# MSXIoT.net
KiCad netlist of a schematic drawn in EAGLE
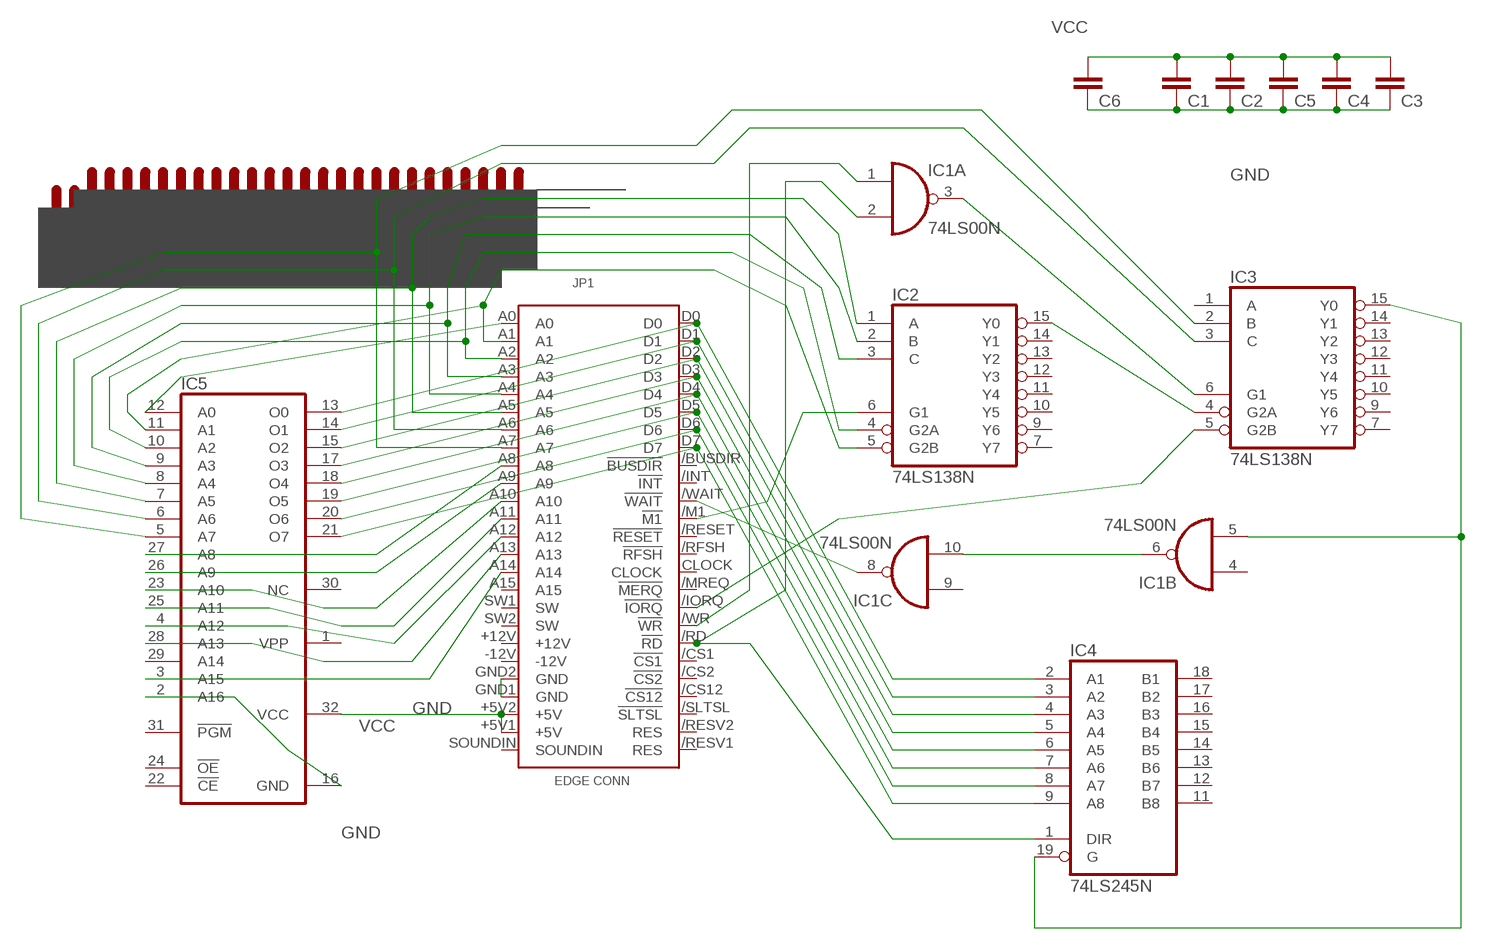
[diagram p0: schematic, sheet 1]

(export (version "E")
  (design (tool "Eeschema 10.0.6"))
  (components
    (comp (ref "C1")
      (value "C2.5/2")
      (footprint "eagle-import:C2.5-2")
      (libsource (lib "eagle-import") (part "C2.5/2"))
    )
    (comp (ref "C2")
      (value "C2,5-3")
      (footprint "eagle-import:C2.5-3")
      (libsource (lib "eagle-import") (part "C2,5-3"))
    )
    (comp (ref "C3")
      (value "C2,5-3")
      (footprint "eagle-import:C2.5-3")
      (libsource (lib "eagle-import") (part "C2,5-3"))
    )
    (comp (ref "C4")
      (value "C2,5-3")
      (footprint "eagle-import:C2.5-3")
      (libsource (lib "eagle-import") (part "C2,5-3"))
    )
    (comp (ref "C5")
      (value "C2,5-3")
      (footprint "eagle-import:C2.5-3")
      (libsource (lib "eagle-import") (part "C2,5-3"))
    )
    (comp (ref "C6")
      (value "C2.5/6")
      (footprint "eagle-import:C2.5-6")
      (libsource (lib "eagle-import") (part "C2.5/6"))
    )
    (comp (ref "IC1")
      (value "74LS00N")
      (footprint "eagle-import:DIL14")
      (libsource (lib "eagle-import") (part "7400NLS"))
    )
    (comp (ref "IC2")
      (value "74LS138N")
      (footprint "eagle-import:DIL16")
      (libsource (lib "eagle-import") (part "74138NLS"))
    )
    (comp (ref "IC3")
      (value "74LS138N")
      (footprint "eagle-import:DIL16")
      (libsource (lib "eagle-import") (part "74138NLS"))
    )
    (comp (ref "IC4")
      (value "74LS245N")
      (footprint "eagle-import:DIL20")
      (libsource (lib "eagle-import") (part "74245NLS"))
    )
    (comp (ref "IC5")
      (value "27C1001A")
      (footprint "eagle-import:DIL32")
      (fields (field (name "MPN") "M27C1001-15F1"))
      (libsource (lib "eagle-import") (part "27C1001A"))
    )
    (comp (ref "JP1")
      (value "MSXCART")
      (footprint "eagle-import:MSXCART")
      (libsource (lib "eagle-import") (part "MSXCART"))
    )
  )
  (nets
    (net (code "1") (name "/+12V") (class "Default")
      (node (ref "JP1") (pin "+12V") (pinfunction "+12V_+12V") (pintype "power_in"))
    )
    (net (code "2") (name "/-12V") (class "Default")
      (node (ref "JP1") (pin "-12V") (pinfunction "-12V_-12V") (pintype "power_in"))
    )
    (net (code "3") (name "/GND") (class "Default")
      (node (ref "C1") (pin "2") (pinfunction "2_2") (pintype "passive"))
      (node (ref "C2") (pin "2") (pinfunction "2_2") (pintype "passive"))
      (node (ref "C3") (pin "2") (pinfunction "2_2") (pintype "passive"))
      (node (ref "C4") (pin "2") (pinfunction "2_2") (pintype "passive"))
      (node (ref "C5") (pin "2") (pinfunction "2_2") (pintype "passive"))
      (node (ref "C6") (pin "2") (pinfunction "2_2") (pintype "passive"))
      (node (ref "IC5") (pin "16") (pinfunction "GND_16") (pintype "power_in"))
      (node (ref "IC5") (pin "2") (pinfunction "A16_2") (pintype "input"))
      (node (ref "JP1") (pin "GND1") (pinfunction "GND_GND1") (pintype "power_in"))
      (node (ref "JP1") (pin "GND2") (pinfunction "GND_GND2") (pintype "power_in"))
    )
    (net (code "4") (name "/VCC") (class "Default")
      (node (ref "C1") (pin "1") (pinfunction "1_1") (pintype "passive"))
      (node (ref "C2") (pin "1") (pinfunction "1_1") (pintype "passive"))
      (node (ref "C3") (pin "1") (pinfunction "1_1") (pintype "passive"))
      (node (ref "C4") (pin "1") (pinfunction "1_1") (pintype "passive"))
      (node (ref "C5") (pin "1") (pinfunction "1_1") (pintype "passive"))
      (node (ref "C6") (pin "1") (pinfunction "1_1") (pintype "passive"))
      (node (ref "IC5") (pin "32") (pinfunction "VCC_32") (pintype "power_in"))
      (node (ref "JP1") (pin "+5V1") (pinfunction "+5V_+5V1") (pintype "power_in"))
      (node (ref "JP1") (pin "+5V2") (pinfunction "+5V_+5V2") (pintype "power_in"))
    )
    (net (code "5") (name "Net-(IC1A-I0)") (class "Default")
      (node (ref "IC1") (pin "1") (pinfunction "I0_1") (pintype "input"))
      (node (ref "JP1") (pin "/WR") (pinfunction "~{WR}_/WR") (pintype "output"))
    )
    (net (code "6") (name "Net-(IC1A-I1)") (class "Default")
      (node (ref "IC1") (pin "2") (pinfunction "I1_2") (pintype "input"))
      (node (ref "IC4") (pin "1") (pinfunction "DIR_1") (pintype "input"))
      (node (ref "JP1") (pin "/RD") (pinfunction "~{RD}_/RD") (pintype "output"))
    )
    (net (code "7") (name "Net-(IC1A-O)") (class "Default")
      (node (ref "IC1") (pin "3") (pinfunction "O_3") (pintype "output"))
      (node (ref "IC3") (pin "6") (pinfunction "G1_6") (pintype "input"))
    )
    (net (code "8") (name "Net-(IC1B-I1)") (class "Default")
      (node (ref "IC1") (pin "5") (pinfunction "I1_5") (pintype "input"))
      (node (ref "IC3") (pin "15") (pinfunction "Y0_15") (pintype "output"))
      (node (ref "IC4") (pin "19") (pinfunction "G_19") (pintype "input"))
    )
    (net (code "9") (name "Net-(IC1B-O)") (class "Default")
      (node (ref "IC1") (pin "10") (pinfunction "I1_10") (pintype "input"))
      (node (ref "IC1") (pin "6") (pinfunction "O_6") (pintype "output"))
    )
    (net (code "10") (name "Net-(IC1C-O)") (class "Default")
      (node (ref "IC1") (pin "8") (pinfunction "O_8") (pintype "output"))
      (node (ref "JP1") (pin "/WAIT") (pinfunction "~{WAIT}_/WAIT") (pintype "open_collector"))
    )
    (net (code "11") (name "Net-(IC2A-A)") (class "Default")
      (node (ref "IC2") (pin "1") (pinfunction "A_1") (pintype "input"))
      (node (ref "IC5") (pin "7") (pinfunction "A5_7") (pintype "input"))
      (node (ref "JP1") (pin "A5") (pinfunction "A5_A5") (pintype "output"))
    )
    (net (code "12") (name "Net-(IC2A-B)") (class "Default")
      (node (ref "IC2") (pin "2") (pinfunction "B_2") (pintype "input"))
      (node (ref "IC5") (pin "8") (pinfunction "A4_8") (pintype "input"))
      (node (ref "JP1") (pin "A4") (pinfunction "A4_A4") (pintype "output"))
    )
    (net (code "13") (name "Net-(IC2A-C)") (class "Default")
      (node (ref "IC2") (pin "3") (pinfunction "C_3") (pintype "input"))
      (node (ref "IC5") (pin "9") (pinfunction "A3_9") (pintype "input"))
      (node (ref "JP1") (pin "A3") (pinfunction "A3_A3") (pintype "output"))
    )
    (net (code "14") (name "Net-(IC2A-G1)") (class "Default")
      (node (ref "IC2") (pin "6") (pinfunction "G1_6") (pintype "input"))
      (node (ref "JP1") (pin "/M1") (pinfunction "~{M1}_/M1") (pintype "output"))
    )
    (net (code "15") (name "Net-(IC2A-G2A)") (class "Default")
      (node (ref "IC2") (pin "4") (pinfunction "G2A_4") (pintype "input"))
      (node (ref "IC5") (pin "10") (pinfunction "A2_10") (pintype "input"))
      (node (ref "JP1") (pin "A2") (pinfunction "A2_A2") (pintype "output"))
    )
    (net (code "16") (name "Net-(IC2A-G2B)") (class "Default")
      (node (ref "IC2") (pin "5") (pinfunction "G2B_5") (pintype "input"))
      (node (ref "IC5") (pin "11") (pinfunction "A1_11") (pintype "input"))
      (node (ref "JP1") (pin "A1") (pinfunction "A1_A1") (pintype "output"))
    )
    (net (code "17") (name "Net-(IC2A-Y0)") (class "Default")
      (node (ref "IC2") (pin "15") (pinfunction "Y0_15") (pintype "output"))
      (node (ref "IC3") (pin "4") (pinfunction "G2A_4") (pintype "input"))
    )
    (net (code "18") (name "Net-(IC3A-B)") (class "Default")
      (node (ref "IC3") (pin "2") (pinfunction "B_2") (pintype "input"))
      (node (ref "IC5") (pin "5") (pinfunction "A7_5") (pintype "input"))
      (node (ref "JP1") (pin "A7") (pinfunction "A7_A7") (pintype "output"))
    )
    (net (code "19") (name "Net-(IC3A-C)") (class "Default")
      (node (ref "IC3") (pin "3") (pinfunction "C_3") (pintype "input"))
      (node (ref "IC5") (pin "6") (pinfunction "A6_6") (pintype "input"))
      (node (ref "JP1") (pin "A6") (pinfunction "A6_A6") (pintype "output"))
    )
    (net (code "20") (name "Net-(IC3A-G2B)") (class "Default")
      (node (ref "IC3") (pin "5") (pinfunction "G2B_5") (pintype "input"))
      (node (ref "JP1") (pin "/IORQ") (pinfunction "~{IORQ}_/IORQ") (pintype "output"))
    )
    (net (code "21") (name "Net-(IC4A-A1)") (class "Default")
      (node (ref "IC4") (pin "2") (pinfunction "A1_2") (pintype "bidirectional"))
      (node (ref "IC5") (pin "13") (pinfunction "O0_13") (pintype "tri_state"))
      (node (ref "JP1") (pin "D0") (pinfunction "D0_D0") (pintype "bidirectional"))
    )
    (net (code "22") (name "Net-(IC4A-A2)") (class "Default")
      (node (ref "IC4") (pin "3") (pinfunction "A2_3") (pintype "bidirectional"))
      (node (ref "IC5") (pin "14") (pinfunction "O1_14") (pintype "tri_state"))
      (node (ref "JP1") (pin "D1") (pinfunction "D1_D1") (pintype "bidirectional"))
    )
    (net (code "23") (name "Net-(IC4A-A3)") (class "Default")
      (node (ref "IC4") (pin "4") (pinfunction "A3_4") (pintype "bidirectional"))
      (node (ref "IC5") (pin "15") (pinfunction "O2_15") (pintype "tri_state"))
      (node (ref "JP1") (pin "D2") (pinfunction "D2_D2") (pintype "bidirectional"))
    )
    (net (code "24") (name "Net-(IC4A-A4)") (class "Default")
      (node (ref "IC4") (pin "5") (pinfunction "A4_5") (pintype "bidirectional"))
      (node (ref "IC5") (pin "17") (pinfunction "O3_17") (pintype "tri_state"))
      (node (ref "JP1") (pin "D3") (pinfunction "D3_D3") (pintype "bidirectional"))
    )
    (net (code "25") (name "Net-(IC4A-A5)") (class "Default")
      (node (ref "IC4") (pin "6") (pinfunction "A5_6") (pintype "bidirectional"))
      (node (ref "IC5") (pin "18") (pinfunction "O4_18") (pintype "tri_state"))
      (node (ref "JP1") (pin "D4") (pinfunction "D4_D4") (pintype "bidirectional"))
    )
    (net (code "26") (name "Net-(IC4A-A6)") (class "Default")
      (node (ref "IC4") (pin "7") (pinfunction "A6_7") (pintype "bidirectional"))
      (node (ref "IC5") (pin "19") (pinfunction "O5_19") (pintype "tri_state"))
      (node (ref "JP1") (pin "D5") (pinfunction "D5_D5") (pintype "bidirectional"))
    )
    (net (code "27") (name "Net-(IC4A-A7)") (class "Default")
      (node (ref "IC4") (pin "8") (pinfunction "A7_8") (pintype "bidirectional"))
      (node (ref "IC5") (pin "20") (pinfunction "O6_20") (pintype "tri_state"))
      (node (ref "JP1") (pin "D6") (pinfunction "D6_D6") (pintype "bidirectional"))
    )
    (net (code "28") (name "Net-(IC4A-A8)") (class "Default")
      (node (ref "IC4") (pin "9") (pinfunction "A8_9") (pintype "bidirectional"))
      (node (ref "IC5") (pin "21") (pinfunction "O7_21") (pintype "tri_state"))
      (node (ref "JP1") (pin "D7") (pinfunction "D7_D7") (pintype "bidirectional"))
    )
    (net (code "29") (name "Net-(IC5-A0)") (class "Default")
      (node (ref "IC5") (pin "12") (pinfunction "A0_12") (pintype "input"))
      (node (ref "JP1") (pin "A0") (pinfunction "A0_A0") (pintype "output"))
    )
    (net (code "30") (name "Net-(IC5-A8)") (class "Default")
      (node (ref "IC5") (pin "27") (pinfunction "A8_27") (pintype "input"))
      (node (ref "JP1") (pin "A8") (pinfunction "A8_A8") (pintype "output"))
    )
    (net (code "31") (name "Net-(IC5-A9)") (class "Default")
      (node (ref "IC5") (pin "26") (pinfunction "A9_26") (pintype "input"))
      (node (ref "JP1") (pin "A9") (pinfunction "A9_A9") (pintype "output"))
    )
    (net (code "32") (name "Net-(IC5-A10)") (class "Default")
      (node (ref "IC5") (pin "23") (pinfunction "A10_23") (pintype "input"))
      (node (ref "JP1") (pin "A10") (pinfunction "A10_A10") (pintype "output"))
    )
    (net (code "33") (name "Net-(IC5-A11)") (class "Default")
      (node (ref "IC5") (pin "25") (pinfunction "A11_25") (pintype "input"))
      (node (ref "JP1") (pin "A11") (pinfunction "A11_A11") (pintype "output"))
    )
    (net (code "34") (name "Net-(IC5-A12)") (class "Default")
      (node (ref "IC5") (pin "4") (pinfunction "A12_4") (pintype "input"))
      (node (ref "JP1") (pin "A12") (pinfunction "A12_A12") (pintype "output"))
    )
    (net (code "35") (name "Net-(IC5-A13)") (class "Default")
      (node (ref "IC5") (pin "28") (pinfunction "A13_28") (pintype "input"))
      (node (ref "JP1") (pin "A13") (pinfunction "A13_A13") (pintype "output"))
    )
    (net (code "36") (name "Net-(IC5-A15)") (class "Default")
      (node (ref "IC5") (pin "3") (pinfunction "A15_3") (pintype "input"))
      (node (ref "JP1") (pin "A14") (pinfunction "A14_A14") (pintype "output"))
    )
    (net (code "37") (name "unconnected-(IC1B-I0-Pad4)") (class "Default")
      (node (ref "IC1") (pin "4") (pinfunction "I0_4") (pintype "input"))
    )
    (net (code "38") (name "unconnected-(IC1C-I0-Pad9)") (class "Default")
      (node (ref "IC1") (pin "9") (pinfunction "I0_9") (pintype "input"))
    )
    (net (code "39") (name "unconnected-(IC2A-Y1-Pad14)") (class "Default")
      (node (ref "IC2") (pin "14") (pinfunction "Y1_14") (pintype "output"))
    )
    (net (code "40") (name "unconnected-(IC2A-Y2-Pad13)") (class "Default")
      (node (ref "IC2") (pin "13") (pinfunction "Y2_13") (pintype "output"))
    )
    (net (code "41") (name "unconnected-(IC2A-Y3-Pad12)") (class "Default")
      (node (ref "IC2") (pin "12") (pinfunction "Y3_12") (pintype "output"))
    )
    (net (code "42") (name "unconnected-(IC2A-Y4-Pad11)") (class "Default")
      (node (ref "IC2") (pin "11") (pinfunction "Y4_11") (pintype "output"))
    )
    (net (code "43") (name "unconnected-(IC2A-Y5-Pad10)") (class "Default")
      (node (ref "IC2") (pin "10") (pinfunction "Y5_10") (pintype "output"))
    )
    (net (code "44") (name "unconnected-(IC2A-Y6-Pad9)") (class "Default")
      (node (ref "IC2") (pin "9") (pinfunction "Y6_9") (pintype "output"))
    )
    (net (code "45") (name "unconnected-(IC2A-Y7-Pad7)") (class "Default")
      (node (ref "IC2") (pin "7") (pinfunction "Y7_7") (pintype "output"))
    )
    (net (code "46") (name "unconnected-(IC3A-A-Pad1)") (class "Default")
      (node (ref "IC3") (pin "1") (pinfunction "A_1") (pintype "input"))
    )
    (net (code "47") (name "unconnected-(IC3A-Y1-Pad14)") (class "Default")
      (node (ref "IC3") (pin "14") (pinfunction "Y1_14") (pintype "output"))
    )
    (net (code "48") (name "unconnected-(IC3A-Y2-Pad13)") (class "Default")
      (node (ref "IC3") (pin "13") (pinfunction "Y2_13") (pintype "output"))
    )
    (net (code "49") (name "unconnected-(IC3A-Y3-Pad12)") (class "Default")
      (node (ref "IC3") (pin "12") (pinfunction "Y3_12") (pintype "output"))
    )
    (net (code "50") (name "unconnected-(IC3A-Y4-Pad11)") (class "Default")
      (node (ref "IC3") (pin "11") (pinfunction "Y4_11") (pintype "output"))
    )
    (net (code "51") (name "unconnected-(IC3A-Y5-Pad10)") (class "Default")
      (node (ref "IC3") (pin "10") (pinfunction "Y5_10") (pintype "output"))
    )
    (net (code "52") (name "unconnected-(IC3A-Y6-Pad9)") (class "Default")
      (node (ref "IC3") (pin "9") (pinfunction "Y6_9") (pintype "output"))
    )
    (net (code "53") (name "unconnected-(IC3A-Y7-Pad7)") (class "Default")
      (node (ref "IC3") (pin "7") (pinfunction "Y7_7") (pintype "output"))
    )
    (net (code "54") (name "unconnected-(IC4A-B1-Pad18)") (class "Default")
      (node (ref "IC4") (pin "18") (pinfunction "B1_18") (pintype "bidirectional"))
    )
    (net (code "55") (name "unconnected-(IC4A-B2-Pad17)") (class "Default")
      (node (ref "IC4") (pin "17") (pinfunction "B2_17") (pintype "bidirectional"))
    )
    (net (code "56") (name "unconnected-(IC4A-B3-Pad16)") (class "Default")
      (node (ref "IC4") (pin "16") (pinfunction "B3_16") (pintype "bidirectional"))
    )
    (net (code "57") (name "unconnected-(IC4A-B4-Pad15)") (class "Default")
      (node (ref "IC4") (pin "15") (pinfunction "B4_15") (pintype "bidirectional"))
    )
    (net (code "58") (name "unconnected-(IC4A-B5-Pad14)") (class "Default")
      (node (ref "IC4") (pin "14") (pinfunction "B5_14") (pintype "bidirectional"))
    )
    (net (code "59") (name "unconnected-(IC4A-B6-Pad13)") (class "Default")
      (node (ref "IC4") (pin "13") (pinfunction "B6_13") (pintype "bidirectional"))
    )
    (net (code "60") (name "unconnected-(IC4A-B7-Pad12)") (class "Default")
      (node (ref "IC4") (pin "12") (pinfunction "B7_12") (pintype "bidirectional"))
    )
    (net (code "61") (name "unconnected-(IC4A-B8-Pad11)") (class "Default")
      (node (ref "IC4") (pin "11") (pinfunction "B8_11") (pintype "bidirectional"))
    )
    (net (code "62") (name "unconnected-(IC5-A14-Pad29)") (class "Default")
      (node (ref "IC5") (pin "29") (pinfunction "A14_29") (pintype "input"))
    )
    (net (code "63") (name "unconnected-(IC5-NC-Pad30)") (class "Default")
      (node (ref "IC5") (pin "30") (pinfunction "NC_30") (pintype "no_connect"))
    )
    (net (code "64") (name "unconnected-(IC5-VPP-Pad1)") (class "Default")
      (node (ref "IC5") (pin "1") (pinfunction "VPP_1") (pintype "passive"))
    )
    (net (code "65") (name "unconnected-(IC5-~{CE}-Pad22)") (class "Default")
      (node (ref "IC5") (pin "22") (pinfunction "~{CE}_22") (pintype "input"))
    )
    (net (code "66") (name "unconnected-(IC5-~{OE}-Pad24)") (class "Default")
      (node (ref "IC5") (pin "24") (pinfunction "~{OE}_24") (pintype "input"))
    )
    (net (code "67") (name "unconnected-(IC5-~{PGM}-Pad31)") (class "Default")
      (node (ref "IC5") (pin "31") (pinfunction "~{PGM}_31") (pintype "input"))
    )
    (net (code "68") (name "unconnected-(JP1-PadA15)") (class "Default")
      (node (ref "JP1") (pin "A15") (pinfunction "A15_A15") (pintype "output"))
    )
    (net (code "69") (name "unconnected-(JP1-PadCLOCK)") (class "Default")
      (node (ref "JP1") (pin "CLOCK") (pinfunction "CLOCK_CLOCK") (pintype "output"))
    )
    (net (code "70") (name "unconnected-(JP1-PadSOUNDIN)") (class "Default")
      (node (ref "JP1") (pin "SOUNDIN") (pinfunction "SOUNDIN_SOUNDIN") (pintype "passive"))
    )
    (net (code "71") (name "unconnected-(JP1-RES-Pad{slash}RESV1)") (class "Default")
      (node (ref "JP1") (pin "/RESV1") (pinfunction "RES_/RESV1") (pintype "no_connect"))
    )
    (net (code "72") (name "unconnected-(JP1-RES-Pad{slash}RESV2)") (class "Default")
      (node (ref "JP1") (pin "/RESV2") (pinfunction "RES_/RESV2") (pintype "no_connect"))
    )
    (net (code "73") (name "unconnected-(JP1-SW-PadSW1)") (class "Default")
      (node (ref "JP1") (pin "SW1") (pinfunction "SW_SW1") (pintype "passive"))
    )
    (net (code "74") (name "unconnected-(JP1-SW-PadSW2)") (class "Default")
      (node (ref "JP1") (pin "SW2") (pinfunction "SW_SW2") (pintype "passive"))
    )
    (net (code "75") (name "unconnected-(JP1-~{BUSDIR}-Pad{slash}BUSDIR)") (class "Default")
      (node (ref "JP1") (pin "/BUSDIR") (pinfunction "~{BUSDIR}_/BUSDIR") (pintype "input"))
    )
    (net (code "76") (name "unconnected-(JP1-~{CS1}-Pad{slash}CS1)") (class "Default")
      (node (ref "JP1") (pin "/CS1") (pinfunction "~{CS1}_/CS1") (pintype "output"))
    )
    (net (code "77") (name "unconnected-(JP1-~{CS2}-Pad{slash}CS2)") (class "Default")
      (node (ref "JP1") (pin "/CS2") (pinfunction "~{CS2}_/CS2") (pintype "output"))
    )
    (net (code "78") (name "unconnected-(JP1-~{CS12}-Pad{slash}CS12)") (class "Default")
      (node (ref "JP1") (pin "/CS12") (pinfunction "~{CS12}_/CS12") (pintype "output"))
    )
    (net (code "79") (name "unconnected-(JP1-~{INT}-Pad{slash}INT)") (class "Default")
      (node (ref "JP1") (pin "/INT") (pinfunction "~{INT}_/INT") (pintype "open_collector"))
    )
    (net (code "80") (name "unconnected-(JP1-~{MERQ}-Pad{slash}MREQ)") (class "Default")
      (node (ref "JP1") (pin "/MREQ") (pinfunction "~{MERQ}_/MREQ") (pintype "output"))
    )
    (net (code "81") (name "unconnected-(JP1-~{RESET}-Pad{slash}RESET)") (class "Default")
      (node (ref "JP1") (pin "/RESET") (pinfunction "~{RESET}_/RESET") (pintype "output"))
    )
    (net (code "82") (name "unconnected-(JP1-~{RFSH}-Pad{slash}RFSH)") (class "Default")
      (node (ref "JP1") (pin "/RFSH") (pinfunction "~{RFSH}_/RFSH") (pintype "output"))
    )
    (net (code "83") (name "unconnected-(JP1-~{SLTSL}-Pad{slash}SLTSL)") (class "Default")
      (node (ref "JP1") (pin "/SLTSL") (pinfunction "~{SLTSL}_/SLTSL") (pintype "output"))
    )
  )
)
